# EPS_Distribution.net
KiCad netlist of a schematic drawn in Altium Designer
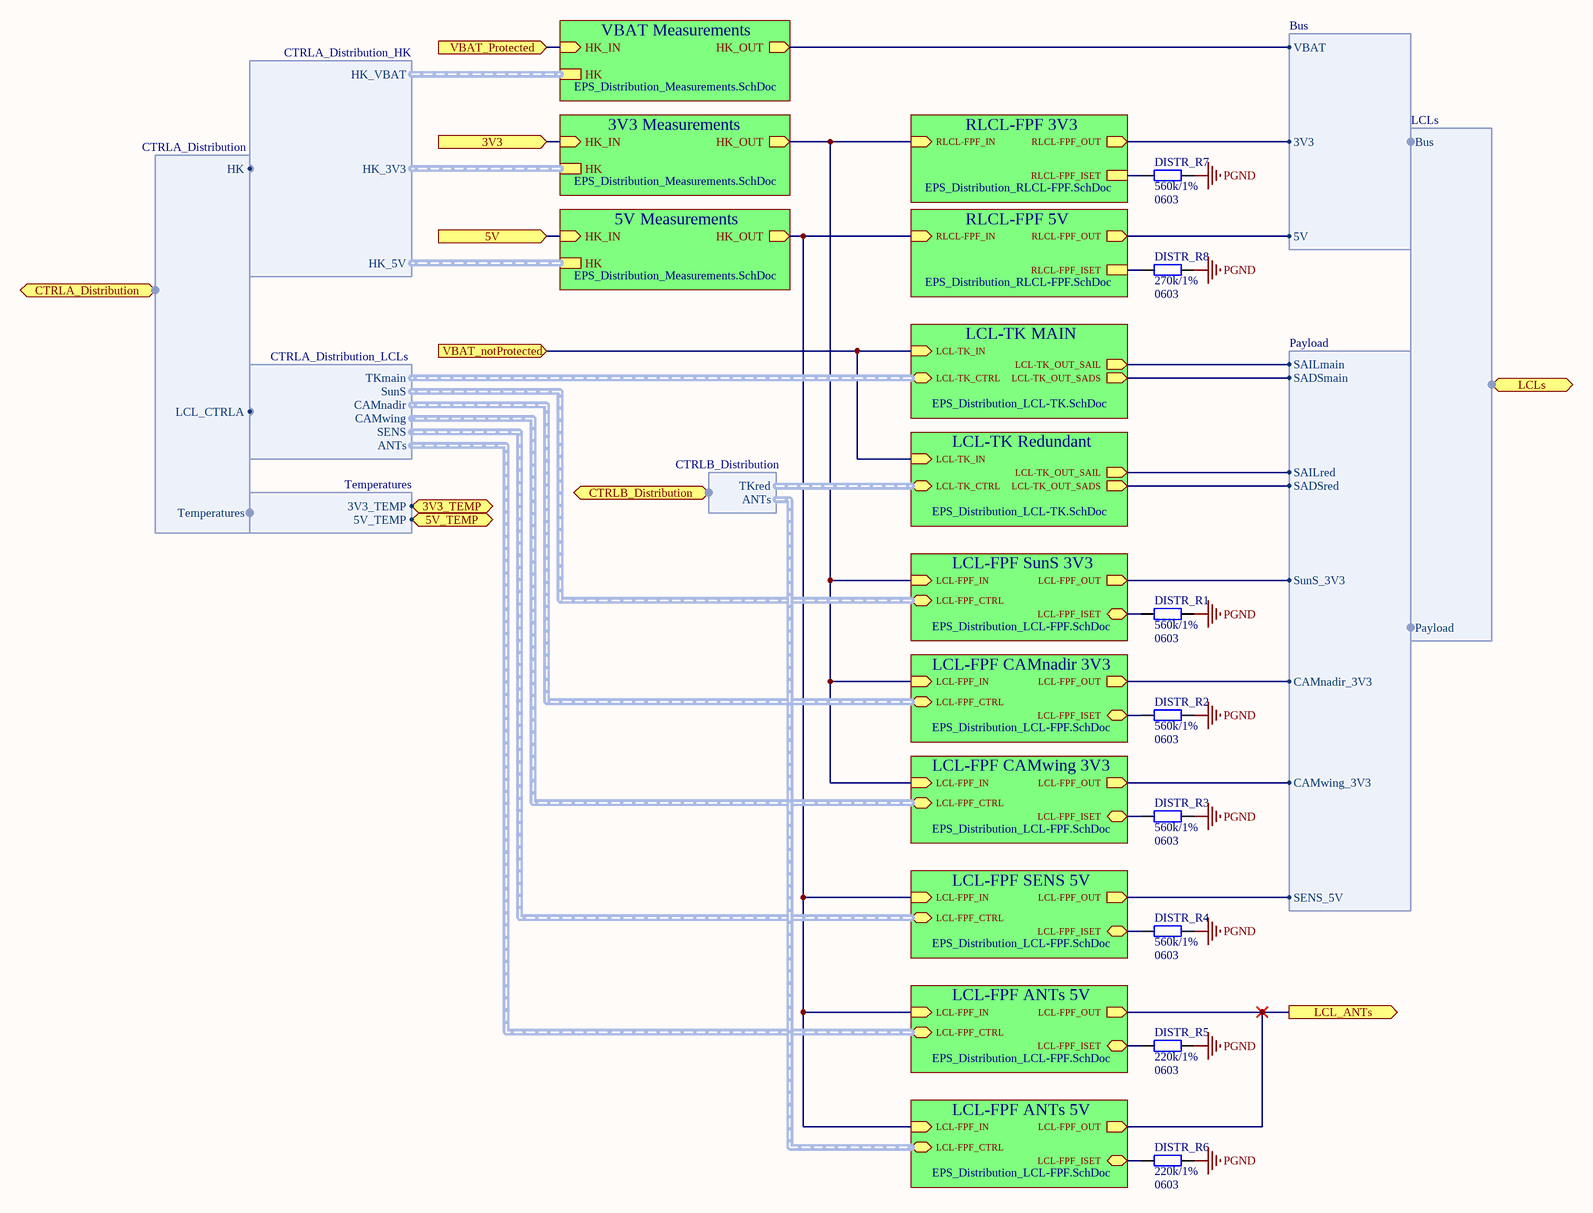
[diagram p0: EPS_Distribution.SchDoc]

(export (version "E")
  (design (tool "Eeschema 10.0.6"))
  (components
    (comp (ref "DISTR_R1")
      (value "560k/1%")
      (footprint "SMD_Resistor_0603")
      (fields (field (name "PACKAGE") "0603"))
      (libsource (lib "resistors") (part "Res"))
    )
    (comp (ref "DISTR_R2")
      (value "560k/1%")
      (footprint "SMD_Resistor_0603")
      (fields (field (name "PACKAGE") "0603"))
      (libsource (lib "resistors") (part "Res"))
    )
    (comp (ref "DISTR_R3")
      (value "560k/1%")
      (footprint "SMD_Resistor_0603")
      (fields (field (name "PACKAGE") "0603"))
      (libsource (lib "resistors") (part "Res"))
    )
    (comp (ref "DISTR_R4")
      (value "560k/1%")
      (footprint "SMD_Resistor_0603")
      (fields (field (name "PACKAGE") "0603"))
      (libsource (lib "resistors") (part "Res"))
    )
    (comp (ref "DISTR_R5")
      (value "220k/1%")
      (footprint "SMD_Resistor_0603")
      (fields (field (name "PACKAGE") "0603"))
      (libsource (lib "resistors") (part "Res"))
    )
    (comp (ref "DISTR_R6")
      (value "220k/1%")
      (footprint "SMD_Resistor_0603")
      (fields (field (name "PACKAGE") "0603"))
      (libsource (lib "resistors") (part "Res"))
    )
    (comp (ref "DISTR_R7")
      (value "560k/1%")
      (footprint "SMD_Resistor_0603")
      (fields (field (name "PACKAGE") "0603"))
      (libsource (lib "resistors") (part "Res"))
    )
    (comp (ref "DISTR_R8")
      (value "270k/1%")
      (footprint "SMD_Resistor_0603")
      (fields (field (name "PACKAGE") "0603"))
      (libsource (lib "resistors") (part "Res"))
    )
  )
  (nets
    (net (code "20") (name "/LCL-FPF_ISET") (class "Default")
      (node (ref "DISTR_R2") (pin "2") (pinfunction "2_2") (pintype "passive"))
    )
    (net (code "21") (name "/LCL-FPF_ISET_1") (class "Default")
      (node (ref "DISTR_R3") (pin "2") (pinfunction "2_2") (pintype "passive"))
    )
    (net (code "22") (name "/LCL-FPF_ISET_2") (class "Default")
      (node (ref "DISTR_R4") (pin "2") (pinfunction "2_2") (pintype "passive"))
    )
    (net (code "23") (name "/LCL-FPF_ISET_3") (class "Default")
      (node (ref "DISTR_R6") (pin "2") (pinfunction "2_2") (pintype "passive"))
    )
    (net (code "24") (name "/LCL-FPF_ISET_4") (class "Default")
      (node (ref "DISTR_R5") (pin "2") (pinfunction "2_2") (pintype "passive"))
    )
    (net (code "25") (name "/LCL-FPF_ISET_5") (class "Default")
      (node (ref "DISTR_R1") (pin "2") (pinfunction "2_2") (pintype "passive"))
    )
    (net (code "36") (name "/RLCL-FPF_ISET") (class "Default")
      (node (ref "DISTR_R8") (pin "2") (pinfunction "2_2") (pintype "passive"))
    )
    (net (code "37") (name "/RLCL-FPF_ISET_1") (class "Default")
      (node (ref "DISTR_R7") (pin "2") (pinfunction "2_2") (pintype "passive"))
    )
    (net (code "47") (name "PGND") (class "Default")
      (node (ref "DISTR_R1") (pin "1") (pinfunction "1_1") (pintype "passive"))
      (node (ref "DISTR_R2") (pin "1") (pinfunction "1_1") (pintype "passive"))
      (node (ref "DISTR_R3") (pin "1") (pinfunction "1_1") (pintype "passive"))
      (node (ref "DISTR_R4") (pin "1") (pinfunction "1_1") (pintype "passive"))
      (node (ref "DISTR_R5") (pin "1") (pinfunction "1_1") (pintype "passive"))
      (node (ref "DISTR_R6") (pin "1") (pinfunction "1_1") (pintype "passive"))
      (node (ref "DISTR_R7") (pin "1") (pinfunction "1_1") (pintype "passive"))
      (node (ref "DISTR_R8") (pin "1") (pinfunction "1_1") (pintype "passive"))
    )
  )
)
